# Sen.net
KiCad netlist of a schematic drawn in EAGLE
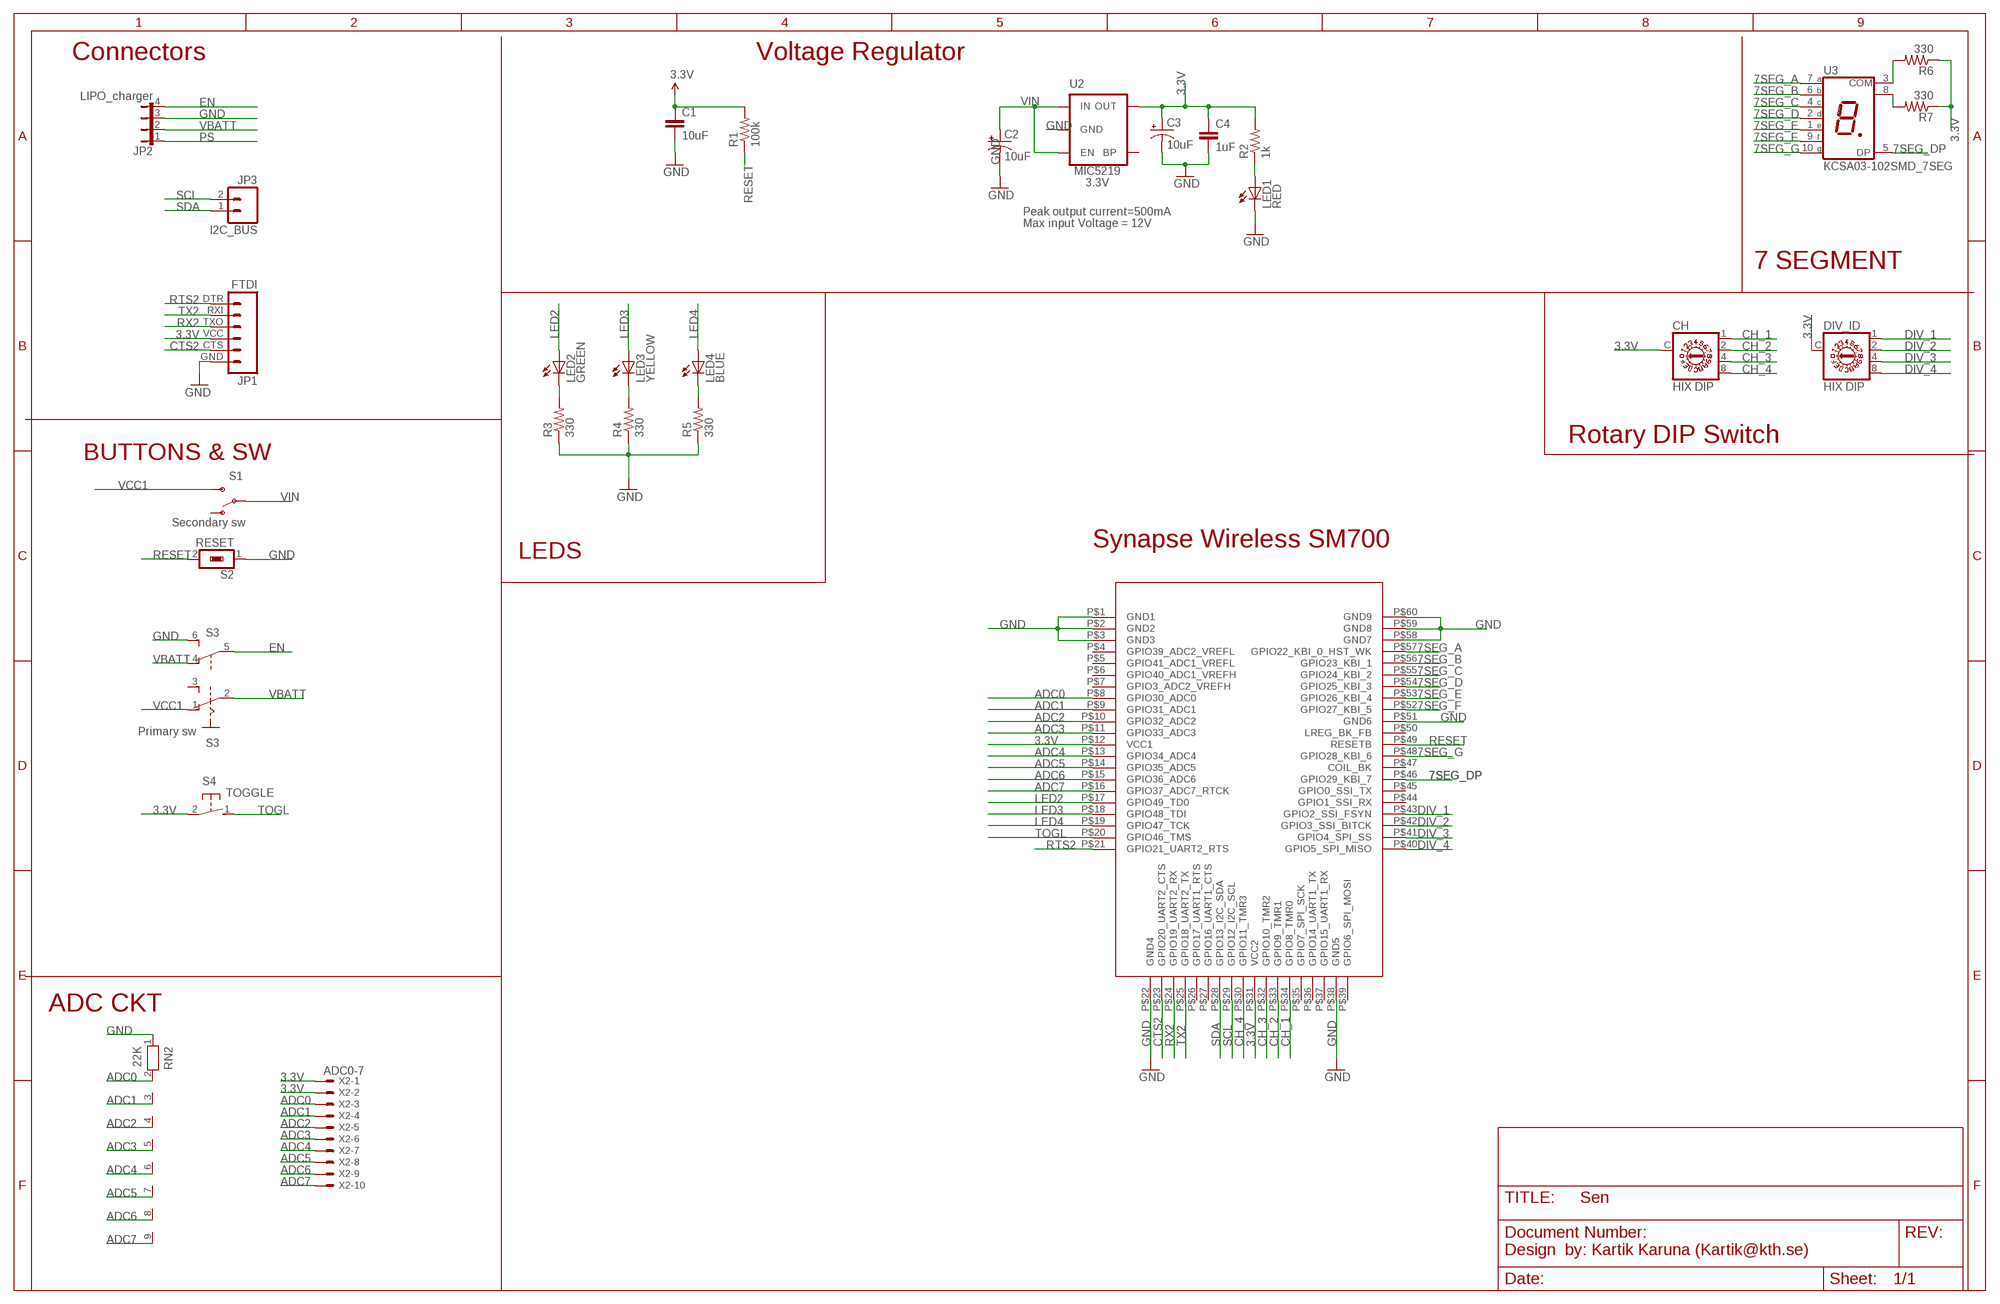
[diagram p0: schematic, sheet 1]

(export (version "E")
  (design (tool "Eeschema 10.0.6"))
  (components
    (comp (ref "C1")
      (value "10uF")
      (footprint "eagle-import:0402-CAP")
      (libsource (lib "eagle-import") (part "CAP0402-CAP"))
    )
    (comp (ref "C2")
      (value "10uF")
      (footprint "eagle-import:EIA3216")
      (libsource (lib "eagle-import") (part "CAP_POL1206"))
    )
    (comp (ref "C3")
      (value "10uF")
      (footprint "eagle-import:EIA3216")
      (libsource (lib "eagle-import") (part "CAP_POL1206"))
    )
    (comp (ref "C4")
      (value "1uF")
      (footprint "eagle-import:0402-CAP")
      (libsource (lib "eagle-import") (part "CAP0402-CAP"))
    )
    (comp (ref "CH")
      (value "HIX DIP")
      (footprint "eagle-import:A1353HEX")
      (libsource (lib "eagle-import") (part "A1353HEX"))
    )
    (comp (ref "DIV_ID")
      (value "HIX DIP")
      (footprint "eagle-import:A1353HEX")
      (libsource (lib "eagle-import") (part "A1353HEX"))
    )
    (comp (ref "JP1")
      (value "FTDI")
      (footprint "eagle-import:FTDI_BASIC")
      (libsource (lib "eagle-import") (part "FTDI_BASICPTH"))
    )
    (comp (ref "JP2")
      (value "LIPO_charger")
      (footprint "eagle-import:JP4")
      (libsource (lib "eagle-import") (part "JP4E"))
    )
    (comp (ref "JP3")
      (value "I2C_BUS")
      (footprint "eagle-import:1X02_NO_SILK")
      (libsource (lib "eagle-import") (part "M021X02_NO_SILK"))
    )
    (comp (ref "LED1")
      (value "RED")
      (footprint "eagle-import:LED-0603")
      (libsource (lib "eagle-import") (part "LED0603"))
    )
    (comp (ref "LED2")
      (value "GREEN")
      (footprint "eagle-import:LED-0603")
      (libsource (lib "eagle-import") (part "LED0603"))
    )
    (comp (ref "LED3")
      (value "YELLOW")
      (footprint "eagle-import:LED-0603")
      (libsource (lib "eagle-import") (part "LED0603"))
    )
    (comp (ref "LED4")
      (value "BLUE")
      (footprint "eagle-import:LED-0603")
      (libsource (lib "eagle-import") (part "LED0603"))
    )
    (comp (ref "R1")
      (value "100k")
      (footprint "eagle-import:0402-RES")
      (libsource (lib "eagle-import") (part "RESISTOR0402-RES"))
    )
    (comp (ref "R2")
      (value "1k")
      (footprint "eagle-import:0402-RES")
      (libsource (lib "eagle-import") (part "RESISTOR0402-RES"))
    )
    (comp (ref "R3")
      (value "330")
      (footprint "eagle-import:0402-RES")
      (libsource (lib "eagle-import") (part "RESISTOR0402-RES"))
    )
    (comp (ref "R4")
      (value "330")
      (footprint "eagle-import:0402-RES")
      (libsource (lib "eagle-import") (part "RESISTOR0402-RES"))
    )
    (comp (ref "R5")
      (value "330")
      (footprint "eagle-import:0402-RES")
      (libsource (lib "eagle-import") (part "RESISTOR0402-RES"))
    )
    (comp (ref "R6")
      (value "330")
      (footprint "eagle-import:0402-RES")
      (libsource (lib "eagle-import") (part "RESISTOR0402-RES"))
    )
    (comp (ref "R7")
      (value "330")
      (footprint "eagle-import:0402-RES")
      (libsource (lib "eagle-import") (part "RESISTOR0402-RES"))
    )
    (comp (ref "RN2")
      (value "22K")
      (footprint "eagle-import:RN-9")
      (libsource (lib "eagle-import") (part "RN08"))
    )
    (comp (ref "S1")
      (value "Secondary sw")
      (footprint "eagle-import:AYZ0202")
      (libsource (lib "eagle-import") (part "SWITCH-SPDTSMD"))
    )
    (comp (ref "S2")
      (value "RESET")
      (footprint "eagle-import:TYCO_FSM")
      (libsource (lib "eagle-import") (part "TYCO_FSMSFSMSM"))
    )
    (comp (ref "S3")
      (value "Primary sw")
      (footprint "eagle-import:A68-A31")
      (libsource (lib "eagle-import") (part "A68-A31"))
    )
    (comp (ref "S4")
      (value "TOGGLE")
      (footprint "eagle-import:TYCO_FSMRACDA")
      (libsource (lib "eagle-import") (part "TYCO_FSMRACDA"))
    )
    (comp (ref "U1")
      (value "SM700PC1SMD")
      (footprint "eagle-import:SYNAPSE_SN700PC1")
      (libsource (lib "eagle-import") (part "SM700PC1SMD"))
    )
    (comp (ref "U2")
      (value "MIC5219")
      (footprint "eagle-import:SOT23-5")
      (libsource (lib "eagle-import") (part "V_REG_LDOSMD"))
    )
    (comp (ref "U3")
      (value "KCSA03-102SMD_7SEG")
      (footprint "eagle-import:SMD-7SEG")
      (libsource (lib "eagle-import") (part "KCSA03-102SMD_7SEG"))
    )
    (comp (ref "X2")
      (value "ADC0-7")
      (footprint "eagle-import:53047-10")
      (fields (field (name "MF") "MOLEX") (field (name "MPN") "53047-1010"))
      (libsource (lib "eagle-import") (part "53?-10047"))
    )
  )
  (nets
    (net (code "1") (name "/7SEG_A") (class "Default")
      (node (ref "U1") (pin "P$57") (pinfunction "GPIO22_KBI_0_HST_WK_P$57") (pintype "bidirectional"))
      (node (ref "U3") (pin "7") (pinfunction "A_7") (pintype "passive"))
    )
    (net (code "2") (name "/7SEG_B") (class "Default")
      (node (ref "U1") (pin "P$56") (pinfunction "GPIO23_KBI_1_P$56") (pintype "bidirectional"))
      (node (ref "U3") (pin "6") (pinfunction "B_6") (pintype "passive"))
    )
    (net (code "3") (name "/7SEG_C") (class "Default")
      (node (ref "U1") (pin "P$55") (pinfunction "GPIO24_KBI_2_P$55") (pintype "bidirectional"))
      (node (ref "U3") (pin "4") (pinfunction "C_4") (pintype "passive"))
    )
    (net (code "4") (name "/7SEG_D") (class "Default")
      (node (ref "U1") (pin "P$54") (pinfunction "GPIO25_KBI_3_P$54") (pintype "bidirectional"))
      (node (ref "U3") (pin "2") (pinfunction "D_2") (pintype "passive"))
    )
    (net (code "5") (name "/7SEG_DP") (class "Default")
      (node (ref "U1") (pin "P$46") (pinfunction "GPIO29_KBI_7_P$46") (pintype "bidirectional"))
      (node (ref "U3") (pin "5") (pinfunction "DP_5") (pintype "passive"))
    )
    (net (code "6") (name "/7SEG_E") (class "Default")
      (node (ref "U1") (pin "P$53") (pinfunction "GPIO26_KBI_4_P$53") (pintype "bidirectional"))
      (node (ref "U3") (pin "1") (pinfunction "E_1") (pintype "passive"))
    )
    (net (code "7") (name "/7SEG_F") (class "Default")
      (node (ref "U1") (pin "P$52") (pinfunction "GPIO27_KBI_5_P$52") (pintype "bidirectional"))
      (node (ref "U3") (pin "9") (pinfunction "F_9") (pintype "passive"))
    )
    (net (code "8") (name "/7SEG_G") (class "Default")
      (node (ref "U1") (pin "P$48") (pinfunction "GPIO28_KBI_6_P$48") (pintype "bidirectional"))
      (node (ref "U3") (pin "10") (pinfunction "G_10") (pintype "passive"))
    )
    (net (code "9") (name "/ADC0") (class "Default")
      (node (ref "RN2") (pin "2") (pinfunction "2_2") (pintype "passive"))
      (node (ref "U1") (pin "P$8") (pinfunction "GPIO30_ADC0_P$8") (pintype "bidirectional"))
      (node (ref "X2") (pin "3") (pinfunction "S_3") (pintype "passive"))
    )
    (net (code "10") (name "/ADC1") (class "Default")
      (node (ref "RN2") (pin "3") (pinfunction "3_3") (pintype "passive"))
      (node (ref "U1") (pin "P$9") (pinfunction "GPIO31_ADC1_P$9") (pintype "bidirectional"))
      (node (ref "X2") (pin "4") (pinfunction "S_4") (pintype "passive"))
    )
    (net (code "11") (name "/ADC2") (class "Default")
      (node (ref "RN2") (pin "4") (pinfunction "4_4") (pintype "passive"))
      (node (ref "U1") (pin "P$10") (pinfunction "GPIO32_ADC2_P$10") (pintype "bidirectional"))
      (node (ref "X2") (pin "5") (pinfunction "S_5") (pintype "passive"))
    )
    (net (code "12") (name "/ADC3") (class "Default")
      (node (ref "RN2") (pin "5") (pinfunction "5_5") (pintype "passive"))
      (node (ref "U1") (pin "P$11") (pinfunction "GPIO33_ADC3_P$11") (pintype "bidirectional"))
      (node (ref "X2") (pin "6") (pinfunction "S_6") (pintype "passive"))
    )
    (net (code "13") (name "/ADC4") (class "Default")
      (node (ref "RN2") (pin "6") (pinfunction "6_6") (pintype "passive"))
      (node (ref "U1") (pin "P$13") (pinfunction "GPIO34_ADC4_P$13") (pintype "bidirectional"))
      (node (ref "X2") (pin "7") (pinfunction "S_7") (pintype "passive"))
    )
    (net (code "14") (name "/ADC5") (class "Default")
      (node (ref "RN2") (pin "7") (pinfunction "7_7") (pintype "passive"))
      (node (ref "U1") (pin "P$14") (pinfunction "GPIO35_ADC5_P$14") (pintype "bidirectional"))
      (node (ref "X2") (pin "8") (pinfunction "S_8") (pintype "passive"))
    )
    (net (code "15") (name "/ADC6") (class "Default")
      (node (ref "RN2") (pin "8") (pinfunction "8_8") (pintype "passive"))
      (node (ref "U1") (pin "P$15") (pinfunction "GPIO36_ADC6_P$15") (pintype "bidirectional"))
      (node (ref "X2") (pin "9") (pinfunction "S_9") (pintype "passive"))
    )
    (net (code "16") (name "/ADC7") (class "Default")
      (node (ref "RN2") (pin "9") (pinfunction "9_9") (pintype "passive"))
      (node (ref "U1") (pin "P$16") (pinfunction "GPIO37_ADC7_RTCK_P$16") (pintype "bidirectional"))
      (node (ref "X2") (pin "10") (pinfunction "S_10") (pintype "passive"))
    )
    (net (code "17") (name "/CH_1") (class "Default")
      (node (ref "CH") (pin "1") (pinfunction "1_1") (pintype "passive"))
      (node (ref "U1") (pin "P$34") (pinfunction "GPIO8_TMR0_P$34") (pintype "bidirectional"))
    )
    (net (code "18") (name "/CH_2") (class "Default")
      (node (ref "CH") (pin "2") (pinfunction "2_2") (pintype "passive"))
      (node (ref "U1") (pin "P$33") (pinfunction "GPIO9_TMR1_P$33") (pintype "bidirectional"))
    )
    (net (code "19") (name "/CH_3") (class "Default")
      (node (ref "CH") (pin "4") (pinfunction "4_4") (pintype "passive"))
      (node (ref "U1") (pin "P$32") (pinfunction "GPIO10_TMR2_P$32") (pintype "bidirectional"))
    )
    (net (code "20") (name "/CH_4") (class "Default")
      (node (ref "CH") (pin "8") (pinfunction "8_8") (pintype "passive"))
      (node (ref "U1") (pin "P$30") (pinfunction "GPIO11_TMR3_P$30") (pintype "bidirectional"))
    )
    (net (code "21") (name "/CTS2") (class "Default")
      (node (ref "JP1") (pin "CTS") (pinfunction "5_CTS") (pintype "passive"))
      (node (ref "U1") (pin "P$23") (pinfunction "GPIO20_UART2_CTS_P$23") (pintype "bidirectional"))
    )
    (net (code "22") (name "/DIV_1") (class "Default")
      (node (ref "DIV_ID") (pin "1") (pinfunction "1_1") (pintype "passive"))
      (node (ref "U1") (pin "P$43") (pinfunction "GPIO2_SSI_FSYN_P$43") (pintype "bidirectional"))
    )
    (net (code "23") (name "/DIV_2") (class "Default")
      (node (ref "DIV_ID") (pin "2") (pinfunction "2_2") (pintype "passive"))
      (node (ref "U1") (pin "P$42") (pinfunction "GPIO3_SSI_BITCK_P$42") (pintype "bidirectional"))
    )
    (net (code "24") (name "/DIV_3") (class "Default")
      (node (ref "DIV_ID") (pin "4") (pinfunction "4_4") (pintype "passive"))
      (node (ref "U1") (pin "P$41") (pinfunction "GPIO4_SPI_SS_P$41") (pintype "bidirectional"))
    )
    (net (code "25") (name "/DIV_4") (class "Default")
      (node (ref "DIV_ID") (pin "8") (pinfunction "8_8") (pintype "passive"))
      (node (ref "U1") (pin "P$40") (pinfunction "GPIO5_SPI_MISO_P$40") (pintype "bidirectional"))
    )
    (net (code "26") (name "/EN") (class "Default")
      (node (ref "JP2") (pin "4") (pinfunction "4_4") (pintype "passive"))
      (node (ref "S3") (pin "5") (pinfunction "P_5") (pintype "passive"))
    )
    (net (code "27") (name "/LED2") (class "Default")
      (node (ref "LED2") (pin "A") (pinfunction "A_A") (pintype "passive"))
      (node (ref "U1") (pin "P$17") (pinfunction "GPIO49_TD0_P$17") (pintype "bidirectional"))
    )
    (net (code "28") (name "/LED3") (class "Default")
      (node (ref "LED3") (pin "A") (pinfunction "A_A") (pintype "passive"))
      (node (ref "U1") (pin "P$18") (pinfunction "GPIO48_TDI_P$18") (pintype "bidirectional"))
    )
    (net (code "29") (name "/LED4") (class "Default")
      (node (ref "LED4") (pin "A") (pinfunction "A_A") (pintype "passive"))
      (node (ref "U1") (pin "P$19") (pinfunction "GPIO47_TCK_P$19") (pintype "bidirectional"))
    )
    (net (code "30") (name "/PS") (class "Default")
      (node (ref "JP2") (pin "1") (pinfunction "1_1") (pintype "passive"))
    )
    (net (code "31") (name "/RESET") (class "Default")
      (node (ref "R1") (pin "1") (pinfunction "1_1") (pintype "passive"))
      (node (ref "S2") (pin "2") (pinfunction "2_2") (pintype "passive"))
      (node (ref "U1") (pin "P$49") (pinfunction "RESETB_P$49") (pintype "bidirectional"))
    )
    (net (code "32") (name "/RTS2") (class "Default")
      (node (ref "JP1") (pin "DTR") (pinfunction "1_DTR") (pintype "passive"))
      (node (ref "U1") (pin "P$21") (pinfunction "GPIO21_UART2_RTS_P$21") (pintype "bidirectional"))
    )
    (net (code "33") (name "/RX2") (class "Default")
      (node (ref "JP1") (pin "TXO") (pinfunction "3_TXO") (pintype "passive"))
      (node (ref "U1") (pin "P$24") (pinfunction "GPIO19_UART2_RX_P$24") (pintype "bidirectional"))
    )
    (net (code "34") (name "/SCL") (class "Default")
      (node (ref "JP3") (pin "2") (pinfunction "2_2") (pintype "passive"))
      (node (ref "U1") (pin "P$29") (pinfunction "GPIO12_I2C_SCL_P$29") (pintype "bidirectional"))
    )
    (net (code "35") (name "/SDA") (class "Default")
      (node (ref "JP3") (pin "1") (pinfunction "1_1") (pintype "passive"))
      (node (ref "U1") (pin "P$28") (pinfunction "GPIO13_I2C_SDA_P$28") (pintype "bidirectional"))
    )
    (net (code "36") (name "/TOGL") (class "Default")
      (node (ref "S4") (pin "1") (pinfunction "1_1") (pintype "passive"))
      (node (ref "U1") (pin "P$20") (pinfunction "GPIO46_TMS_P$20") (pintype "bidirectional"))
    )
    (net (code "37") (name "/TX2") (class "Default")
      (node (ref "JP1") (pin "RXI") (pinfunction "2_RXI") (pintype "passive"))
      (node (ref "U1") (pin "P$25") (pinfunction "GPIO18_UART2_TX_P$25") (pintype "bidirectional"))
    )
    (net (code "38") (name "/VBATT") (class "Default")
      (node (ref "JP2") (pin "2") (pinfunction "2_2") (pintype "passive"))
      (node (ref "S3") (pin "2") (pinfunction "P_2") (pintype "passive"))
      (node (ref "S3") (pin "4") (pinfunction "O_4") (pintype "passive"))
    )
    (net (code "39") (name "/VCC1") (class "Default")
      (node (ref "S1") (pin "3") (pinfunction "S_3") (pintype "passive"))
      (node (ref "S3") (pin "1") (pinfunction "O_1") (pintype "passive"))
    )
    (net (code "40") (name "/VIN") (class "Default")
      (node (ref "C2") (pin "A") (pinfunction "+_A") (pintype "passive"))
      (node (ref "S1") (pin "2") (pinfunction "P_2") (pintype "passive"))
      (node (ref "U2") (pin "1") (pinfunction "IN_1") (pintype "input"))
      (node (ref "U2") (pin "3") (pinfunction "EN_3") (pintype "input"))
    )
    (net (code "41") (name "3.3V") (class "Default")
      (node (ref "C1") (pin "1") (pinfunction "1_1") (pintype "passive"))
      (node (ref "C3") (pin "A") (pinfunction "+_A") (pintype "passive"))
      (node (ref "C4") (pin "1") (pinfunction "1_1") (pintype "passive"))
      (node (ref "CH") (pin "C") (pinfunction "C_C") (pintype "passive"))
      (node (ref "DIV_ID") (pin "C") (pinfunction "C_C") (pintype "passive"))
      (node (ref "JP1") (pin "VCC") (pinfunction "4_VCC") (pintype "passive"))
      (node (ref "R1") (pin "2") (pinfunction "2_2") (pintype "passive"))
      (node (ref "R2") (pin "2") (pinfunction "2_2") (pintype "passive"))
      (node (ref "R6") (pin "1") (pinfunction "1_1") (pintype "passive"))
      (node (ref "R7") (pin "1") (pinfunction "1_1") (pintype "passive"))
      (node (ref "S4") (pin "2") (pinfunction "2_2") (pintype "passive"))
      (node (ref "U1") (pin "P$12") (pinfunction "VCC1_P$12") (pintype "bidirectional"))
      (node (ref "U1") (pin "P$31") (pinfunction "VCC2_P$31") (pintype "bidirectional"))
      (node (ref "U2") (pin "5") (pinfunction "OUT_5") (pintype "passive"))
      (node (ref "X2") (pin "1") (pinfunction "S_1") (pintype "passive"))
      (node (ref "X2") (pin "2") (pinfunction "S_2") (pintype "passive"))
    )
    (net (code "42") (name "GND") (class "Default")
      (node (ref "C1") (pin "2") (pinfunction "2_2") (pintype "passive"))
      (node (ref "C2") (pin "C") (pinfunction "-_C") (pintype "passive"))
      (node (ref "C3") (pin "C") (pinfunction "-_C") (pintype "passive"))
      (node (ref "C4") (pin "2") (pinfunction "2_2") (pintype "passive"))
      (node (ref "JP1") (pin "GND") (pinfunction "6_GND") (pintype "passive"))
      (node (ref "JP2") (pin "3") (pinfunction "3_3") (pintype "passive"))
      (node (ref "LED1") (pin "C") (pinfunction "C_C") (pintype "passive"))
      (node (ref "R3") (pin "1") (pinfunction "1_1") (pintype "passive"))
      (node (ref "R4") (pin "1") (pinfunction "1_1") (pintype "passive"))
      (node (ref "R5") (pin "1") (pinfunction "1_1") (pintype "passive"))
      (node (ref "RN2") (pin "1") (pinfunction "1_1") (pintype "passive"))
      (node (ref "S2") (pin "1") (pinfunction "1_1") (pintype "passive"))
      (node (ref "S3") (pin "6") (pinfunction "S_6") (pintype "passive"))
      (node (ref "U1") (pin "P$1") (pinfunction "GND1_P$1") (pintype "bidirectional"))
      (node (ref "U1") (pin "P$2") (pinfunction "GND2_P$2") (pintype "bidirectional"))
      (node (ref "U1") (pin "P$22") (pinfunction "GND4_P$22") (pintype "bidirectional"))
      (node (ref "U1") (pin "P$3") (pinfunction "GND3_P$3") (pintype "bidirectional"))
      (node (ref "U1") (pin "P$38") (pinfunction "GND5_P$38") (pintype "bidirectional"))
      (node (ref "U1") (pin "P$51") (pinfunction "GND6_P$51") (pintype "bidirectional"))
      (node (ref "U1") (pin "P$58") (pinfunction "GND7_P$58") (pintype "bidirectional"))
      (node (ref "U1") (pin "P$59") (pinfunction "GND8_P$59") (pintype "bidirectional"))
      (node (ref "U1") (pin "P$60") (pinfunction "GND9_P$60") (pintype "bidirectional"))
      (node (ref "U2") (pin "2") (pinfunction "GND_2") (pintype "input"))
    )
    (net (code "43") (name "Net-(LED1-PadA)") (class "Default")
      (node (ref "LED1") (pin "A") (pinfunction "A_A") (pintype "passive"))
      (node (ref "R2") (pin "1") (pinfunction "1_1") (pintype "passive"))
    )
    (net (code "44") (name "Net-(LED2-PadC)") (class "Default")
      (node (ref "LED2") (pin "C") (pinfunction "C_C") (pintype "passive"))
      (node (ref "R3") (pin "2") (pinfunction "2_2") (pintype "passive"))
    )
    (net (code "45") (name "Net-(LED3-PadC)") (class "Default")
      (node (ref "LED3") (pin "C") (pinfunction "C_C") (pintype "passive"))
      (node (ref "R4") (pin "2") (pinfunction "2_2") (pintype "passive"))
    )
    (net (code "46") (name "Net-(LED4-PadC)") (class "Default")
      (node (ref "LED4") (pin "C") (pinfunction "C_C") (pintype "passive"))
      (node (ref "R5") (pin "2") (pinfunction "2_2") (pintype "passive"))
    )
    (net (code "47") (name "Net-(R6-Pad2)") (class "Default")
      (node (ref "R6") (pin "2") (pinfunction "2_2") (pintype "passive"))
      (node (ref "U3") (pin "3") (pinfunction "COM_3") (pintype "passive"))
    )
    (net (code "48") (name "Net-(R7-Pad2)") (class "Default")
      (node (ref "R7") (pin "2") (pinfunction "2_2") (pintype "passive"))
      (node (ref "U3") (pin "8") (pinfunction "COM_8") (pintype "passive"))
    )
    (net (code "49") (name "unconnected-(S1-O-Pad1)") (class "Default")
      (node (ref "S1") (pin "1") (pinfunction "O_1") (pintype "passive"))
    )
    (net (code "50") (name "unconnected-(S3A-S-Pad3)") (class "Default")
      (node (ref "S3") (pin "3") (pinfunction "S_3") (pintype "passive"))
    )
    (net (code "51") (name "unconnected-(U1-COIL_BK-PadP$47)") (class "Default")
      (node (ref "U1") (pin "P$47") (pinfunction "COIL_BK_P$47") (pintype "bidirectional"))
    )
    (net (code "52") (name "unconnected-(U1-GPIO0_SSI_TX-PadP$45)") (class "Default")
      (node (ref "U1") (pin "P$45") (pinfunction "GPIO0_SSI_TX_P$45") (pintype "bidirectional"))
    )
    (net (code "53") (name "unconnected-(U1-GPIO1_SSI_RX-PadP$44)") (class "Default")
      (node (ref "U1") (pin "P$44") (pinfunction "GPIO1_SSI_RX_P$44") (pintype "bidirectional"))
    )
    (net (code "54") (name "unconnected-(U1-GPIO3_ADC2_VREFH-PadP$7)") (class "Default")
      (node (ref "U1") (pin "P$7") (pinfunction "GPIO3_ADC2_VREFH_P$7") (pintype "bidirectional"))
    )
    (net (code "55") (name "unconnected-(U1-GPIO6_SPI_MOSI-PadP$39)") (class "Default")
      (node (ref "U1") (pin "P$39") (pinfunction "GPIO6_SPI_MOSI_P$39") (pintype "bidirectional"))
    )
    (net (code "56") (name "unconnected-(U1-GPIO7_SPI_SCK-PadP$35)") (class "Default")
      (node (ref "U1") (pin "P$35") (pinfunction "GPIO7_SPI_SCK_P$35") (pintype "bidirectional"))
    )
    (net (code "57") (name "unconnected-(U1-GPIO14_UART1_TX-PadP$36)") (class "Default")
      (node (ref "U1") (pin "P$36") (pinfunction "GPIO14_UART1_TX_P$36") (pintype "bidirectional"))
    )
    (net (code "58") (name "unconnected-(U1-GPIO15_UART1_RX-PadP$37)") (class "Default")
      (node (ref "U1") (pin "P$37") (pinfunction "GPIO15_UART1_RX_P$37") (pintype "bidirectional"))
    )
    (net (code "59") (name "unconnected-(U1-GPIO16_UART1_CTS-PadP$27)") (class "Default")
      (node (ref "U1") (pin "P$27") (pinfunction "GPIO16_UART1_CTS_P$27") (pintype "bidirectional"))
    )
    (net (code "60") (name "unconnected-(U1-GPIO17_UART1_RTS-PadP$26)") (class "Default")
      (node (ref "U1") (pin "P$26") (pinfunction "GPIO17_UART1_RTS_P$26") (pintype "bidirectional"))
    )
    (net (code "61") (name "unconnected-(U1-GPIO39_ADC2_VREFL-PadP$4)") (class "Default")
      (node (ref "U1") (pin "P$4") (pinfunction "GPIO39_ADC2_VREFL_P$4") (pintype "bidirectional"))
    )
    (net (code "62") (name "unconnected-(U1-GPIO40_ADC1_VREFH-PadP$6)") (class "Default")
      (node (ref "U1") (pin "P$6") (pinfunction "GPIO40_ADC1_VREFH_P$6") (pintype "bidirectional"))
    )
    (net (code "63") (name "unconnected-(U1-GPIO41_ADC1_VREFL-PadP$5)") (class "Default")
      (node (ref "U1") (pin "P$5") (pinfunction "GPIO41_ADC1_VREFL_P$5") (pintype "bidirectional"))
    )
    (net (code "64") (name "unconnected-(U1-LREG_BK_FB-PadP$50)") (class "Default")
      (node (ref "U1") (pin "P$50") (pinfunction "LREG_BK_FB_P$50") (pintype "bidirectional"))
    )
    (net (code "65") (name "unconnected-(U2-BP-Pad4)") (class "Default")
      (node (ref "U2") (pin "4") (pinfunction "BP_4") (pintype "input"))
    )
  )
)
